# SSC_SCH.net
KiCad netlist of a schematic drawn in EasyEDA
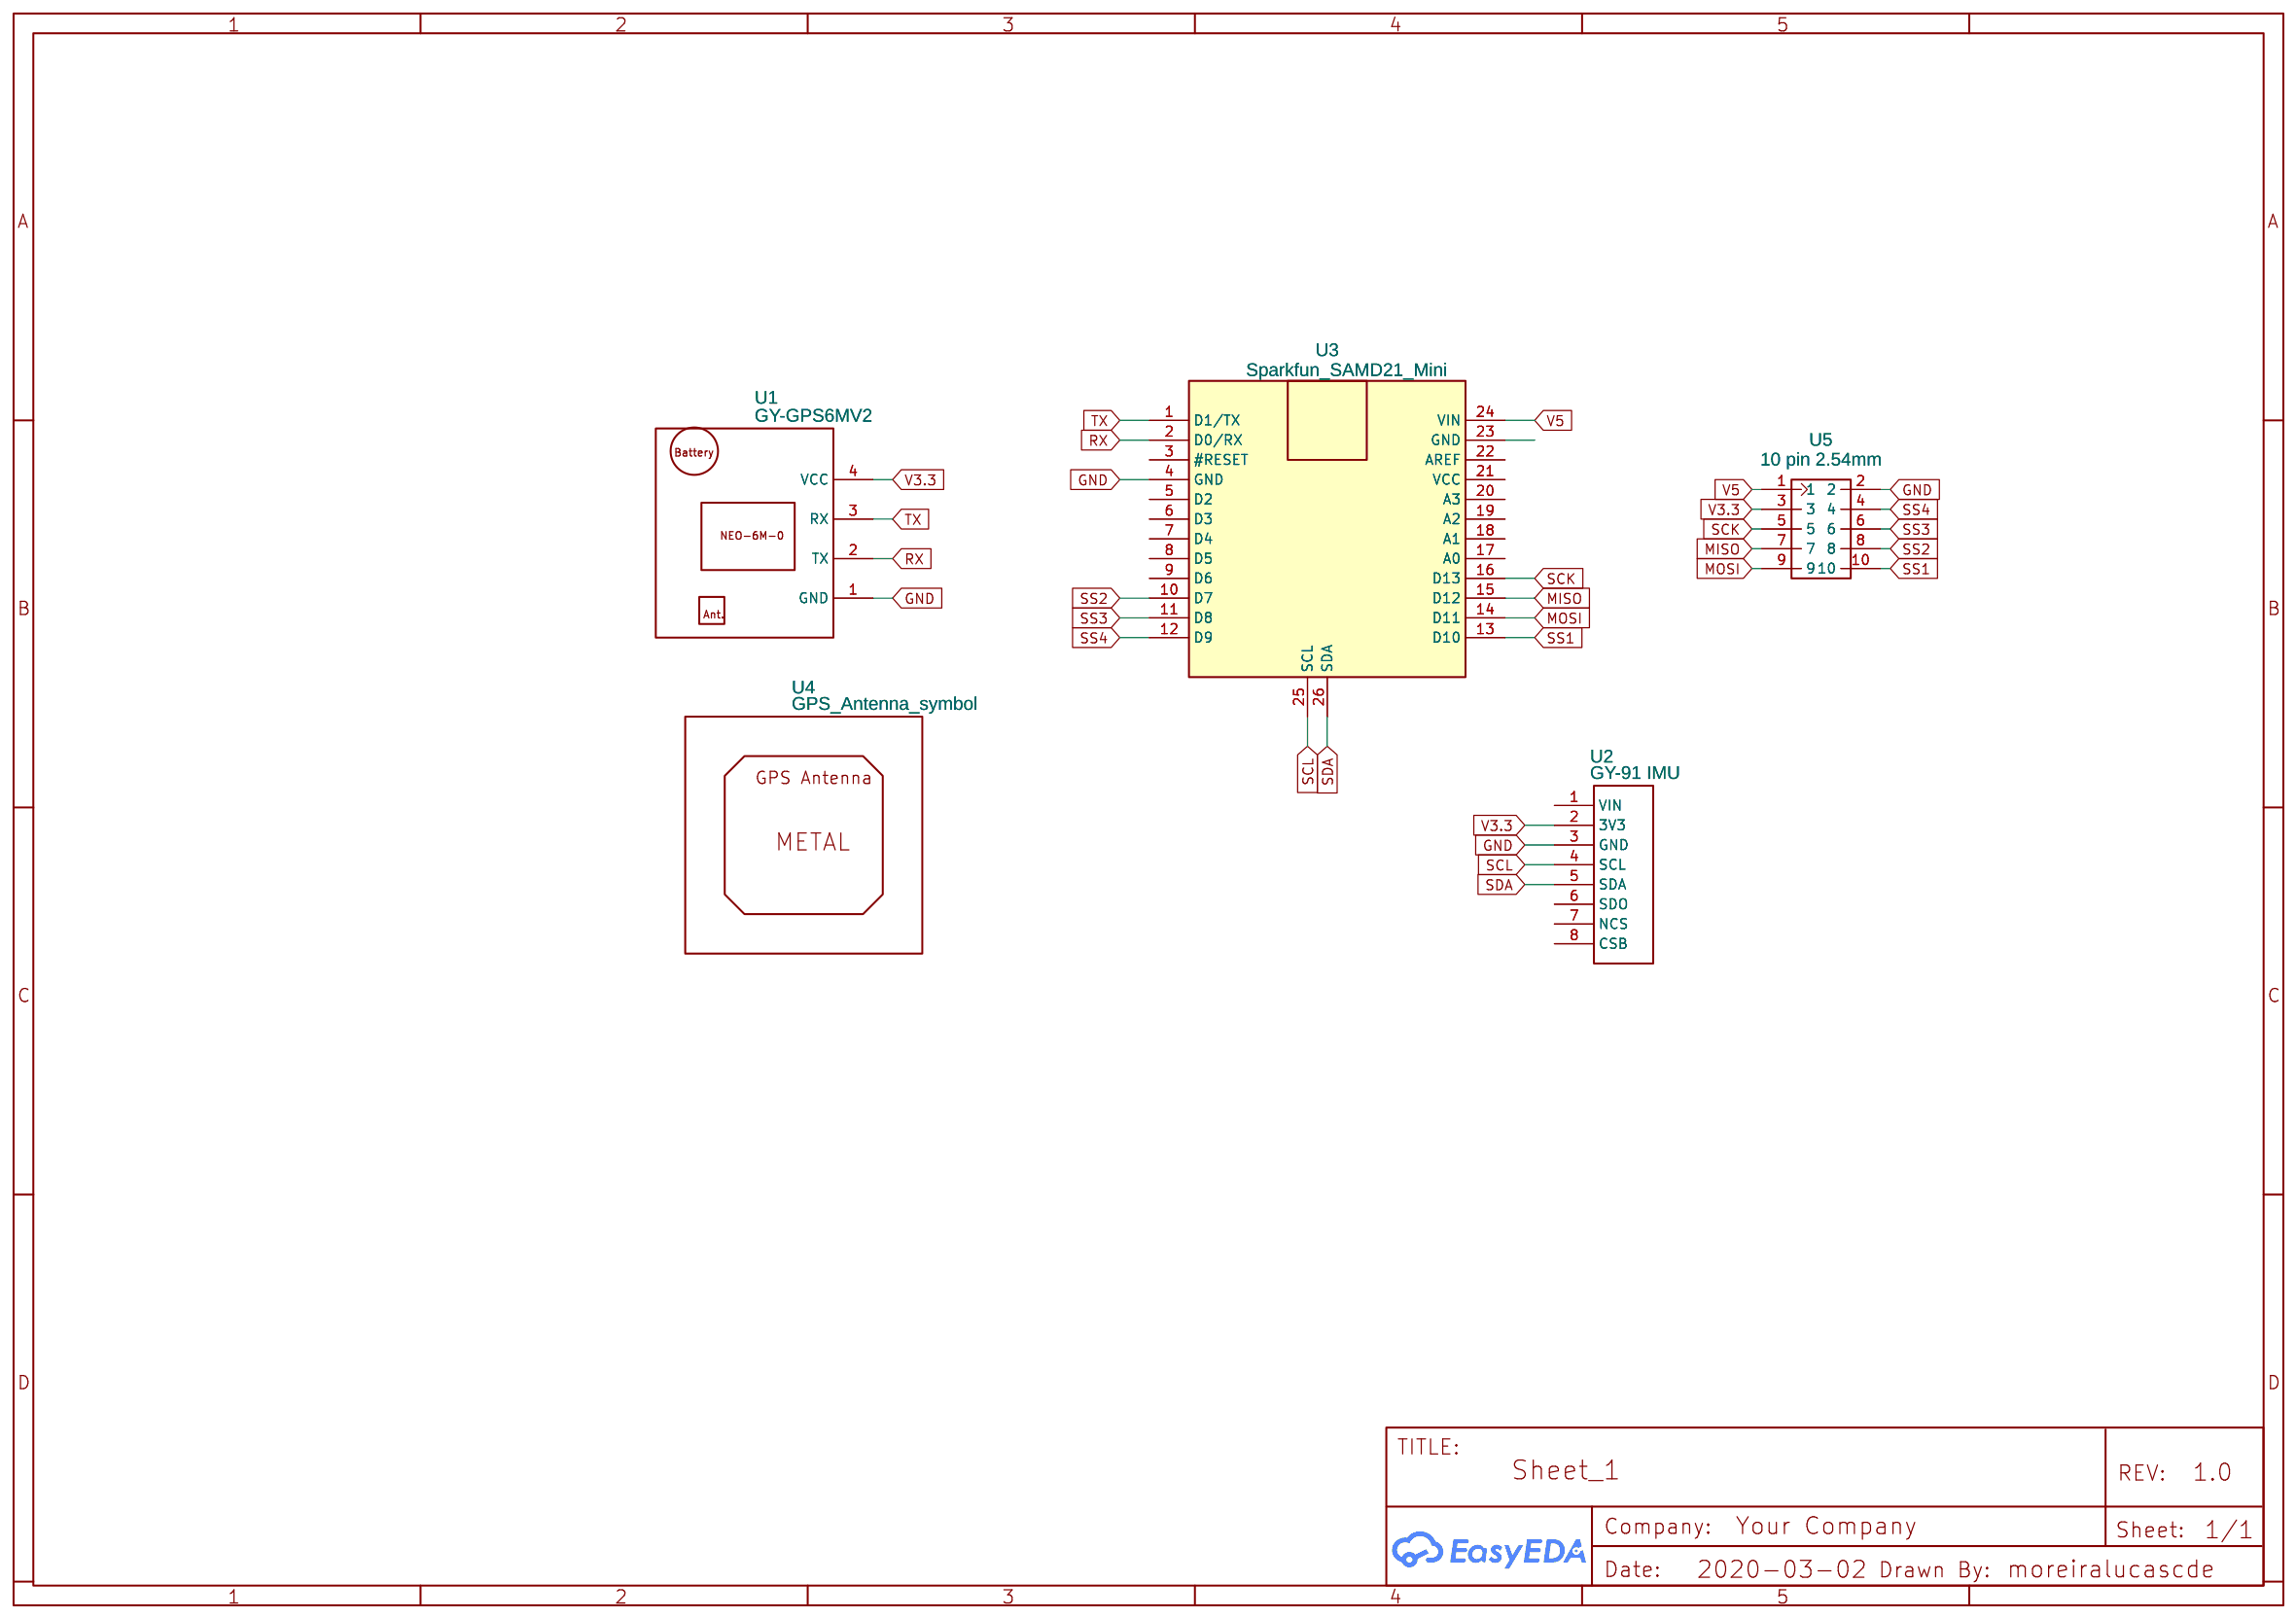
[diagram p0: schematic sheet]

(export (version "E")
  (design (tool "Eeschema 10.0.6"))
  (components
    (comp (ref "U1") (value "GY-GPS6MV2") (libsource (lib "") (part "GY-GPS6MV2")))
    (comp (ref "U2") (value "GY-91 IMU") (libsource (lib "") (part "GY-91")))
    (comp (ref "U3")
      (value "Sparkfun_SAMD21_Mini")
      (fields (field (name "BOM_Manufacturer Part") "New SchematicLib"))
      (libsource (lib "") (part "Sparkfun_SAMD21_Mini"))
    )
    (comp (ref "U4") (value "GPS_Antenna_symbol") (libsource (lib "") (part "GPS_Antenna_symbol")))
    (comp (ref "U5")
      (value "10 pin 2.54mm")
      (fields
        (field (name "BOM_Manufacturer Part") "67997-410HLF")
        (field (name "BOM_Supplier Part") "609-3243-ND")
      )
      (libsource (lib "") (part "10 pin 2.54mm"))
    )
  )
  (nets
    (net (code "1") (name "GND") (class "Default")
      (node (ref "U1") (pin "1") (pinfunction "GND_1") (pintype "unspecified"))
      (node (ref "U2") (pin "3") (pinfunction "GND_3") (pintype "unspecified"))
      (node (ref "U3") (pin "4") (pinfunction "GND_4") (pintype "unspecified"))
      (node (ref "U5") (pin "2") (pinfunction "2_2") (pintype "unspecified"))
    )
    (net (code "2") (name "MISO") (class "Default")
      (node (ref "U3") (pin "15") (pinfunction "D12_15") (pintype "unspecified"))
      (node (ref "U5") (pin "7") (pinfunction "7_7") (pintype "unspecified"))
    )
    (net (code "3") (name "MOSI") (class "Default")
      (node (ref "U3") (pin "14") (pinfunction "D11_14") (pintype "unspecified"))
      (node (ref "U5") (pin "9") (pinfunction "9_9") (pintype "unspecified"))
    )
    (net (code "4") (name "RX") (class "Default")
      (node (ref "U1") (pin "2") (pinfunction "TX_2") (pintype "unspecified"))
      (node (ref "U3") (pin "2") (pinfunction "D0/RX_2") (pintype "unspecified"))
    )
    (net (code "5") (name "SCK") (class "Default")
      (node (ref "U3") (pin "16") (pinfunction "D13_16") (pintype "unspecified"))
      (node (ref "U5") (pin "5") (pinfunction "5_5") (pintype "unspecified"))
    )
    (net (code "6") (name "SCL") (class "Default")
      (node (ref "U2") (pin "4") (pinfunction "SCL_4") (pintype "unspecified"))
      (node (ref "U3") (pin "25") (pinfunction "SCL_25") (pintype "unspecified"))
    )
    (net (code "7") (name "SDA") (class "Default")
      (node (ref "U2") (pin "5") (pinfunction "SDA_5") (pintype "unspecified"))
      (node (ref "U3") (pin "26") (pinfunction "SDA_26") (pintype "unspecified"))
    )
    (net (code "8") (name "SS1") (class "Default")
      (node (ref "U3") (pin "13") (pinfunction "D10_13") (pintype "unspecified"))
      (node (ref "U5") (pin "10") (pinfunction "10_10") (pintype "unspecified"))
    )
    (net (code "9") (name "SS2") (class "Default")
      (node (ref "U3") (pin "10") (pinfunction "D7_10") (pintype "unspecified"))
      (node (ref "U5") (pin "8") (pinfunction "8_8") (pintype "unspecified"))
    )
    (net (code "10") (name "SS3") (class "Default")
      (node (ref "U3") (pin "11") (pinfunction "D8_11") (pintype "unspecified"))
      (node (ref "U5") (pin "6") (pinfunction "6_6") (pintype "unspecified"))
    )
    (net (code "11") (name "SS4") (class "Default")
      (node (ref "U3") (pin "12") (pinfunction "D9_12") (pintype "unspecified"))
      (node (ref "U5") (pin "4") (pinfunction "4_4") (pintype "passive"))
    )
    (net (code "12") (name "TX") (class "Default")
      (node (ref "U1") (pin "3") (pinfunction "RX_3") (pintype "unspecified"))
      (node (ref "U3") (pin "1") (pinfunction "D1/TX_1") (pintype "unspecified"))
    )
    (net (code "13") (name "V3.3") (class "Default")
      (node (ref "U1") (pin "4") (pinfunction "VCC_4") (pintype "unspecified"))
      (node (ref "U2") (pin "2") (pinfunction "3V3_2") (pintype "unspecified"))
      (node (ref "U5") (pin "3") (pinfunction "3_3") (pintype "unspecified"))
    )
    (net (code "14") (name "V5") (class "Default")
      (node (ref "U3") (pin "24") (pinfunction "VIN_24") (pintype "unspecified"))
      (node (ref "U5") (pin "1") (pinfunction "1_1") (pintype "unspecified"))
    )
    (net (code "15") (name "unconnected-(U2-CSB-Pad8)") (class "Default")
      (node (ref "U2") (pin "8") (pinfunction "CSB_8") (pintype "unspecified"))
    )
    (net (code "16") (name "unconnected-(U2-NCS-Pad7)") (class "Default")
      (node (ref "U2") (pin "7") (pinfunction "NCS_7") (pintype "unspecified"))
    )
    (net (code "17") (name "unconnected-(U2-SDO-Pad6)") (class "Default")
      (node (ref "U2") (pin "6") (pinfunction "SDO_6") (pintype "unspecified"))
    )
    (net (code "18") (name "unconnected-(U2-VIN-Pad1)") (class "Default")
      (node (ref "U2") (pin "1") (pinfunction "VIN_1") (pintype "unspecified"))
    )
    (net (code "19") (name "unconnected-(U3-#RESET-Pad3)") (class "Default")
      (node (ref "U3") (pin "3") (pinfunction "#RESET_3") (pintype "unspecified"))
    )
    (net (code "20") (name "unconnected-(U3-A0-Pad17)") (class "Default")
      (node (ref "U3") (pin "17") (pinfunction "A0_17") (pintype "unspecified"))
    )
    (net (code "21") (name "unconnected-(U3-A1-Pad18)") (class "Default")
      (node (ref "U3") (pin "18") (pinfunction "A1_18") (pintype "unspecified"))
    )
    (net (code "22") (name "unconnected-(U3-A2-Pad19)") (class "Default")
      (node (ref "U3") (pin "19") (pinfunction "A2_19") (pintype "unspecified"))
    )
    (net (code "23") (name "unconnected-(U3-A3-Pad20)") (class "Default")
      (node (ref "U3") (pin "20") (pinfunction "A3_20") (pintype "unspecified"))
    )
    (net (code "24") (name "unconnected-(U3-AREF-Pad22)") (class "Default")
      (node (ref "U3") (pin "22") (pinfunction "AREF_22") (pintype "unspecified"))
    )
    (net (code "25") (name "unconnected-(U3-D2-Pad5)") (class "Default")
      (node (ref "U3") (pin "5") (pinfunction "D2_5") (pintype "unspecified"))
    )
    (net (code "26") (name "unconnected-(U3-D3-Pad6)") (class "Default")
      (node (ref "U3") (pin "6") (pinfunction "D3_6") (pintype "unspecified"))
    )
    (net (code "27") (name "unconnected-(U3-D4-Pad7)") (class "Default")
      (node (ref "U3") (pin "7") (pinfunction "D4_7") (pintype "unspecified"))
    )
    (net (code "28") (name "unconnected-(U3-D5-Pad8)") (class "Default")
      (node (ref "U3") (pin "8") (pinfunction "D5_8") (pintype "unspecified"))
    )
    (net (code "29") (name "unconnected-(U3-D6-Pad9)") (class "Default")
      (node (ref "U3") (pin "9") (pinfunction "D6_9") (pintype "unspecified"))
    )
    (net (code "30") (name "unconnected-(U3-GND-Pad23)") (class "Default")
      (node (ref "U3") (pin "23") (pinfunction "GND_23") (pintype "unspecified"))
    )
    (net (code "31") (name "unconnected-(U3-VCC-Pad21)") (class "Default")
      (node (ref "U3") (pin "21") (pinfunction "VCC_21") (pintype "unspecified"))
    )
  )
)
